# Headstage.net
KiCad netlist of a schematic drawn in Altium Designer
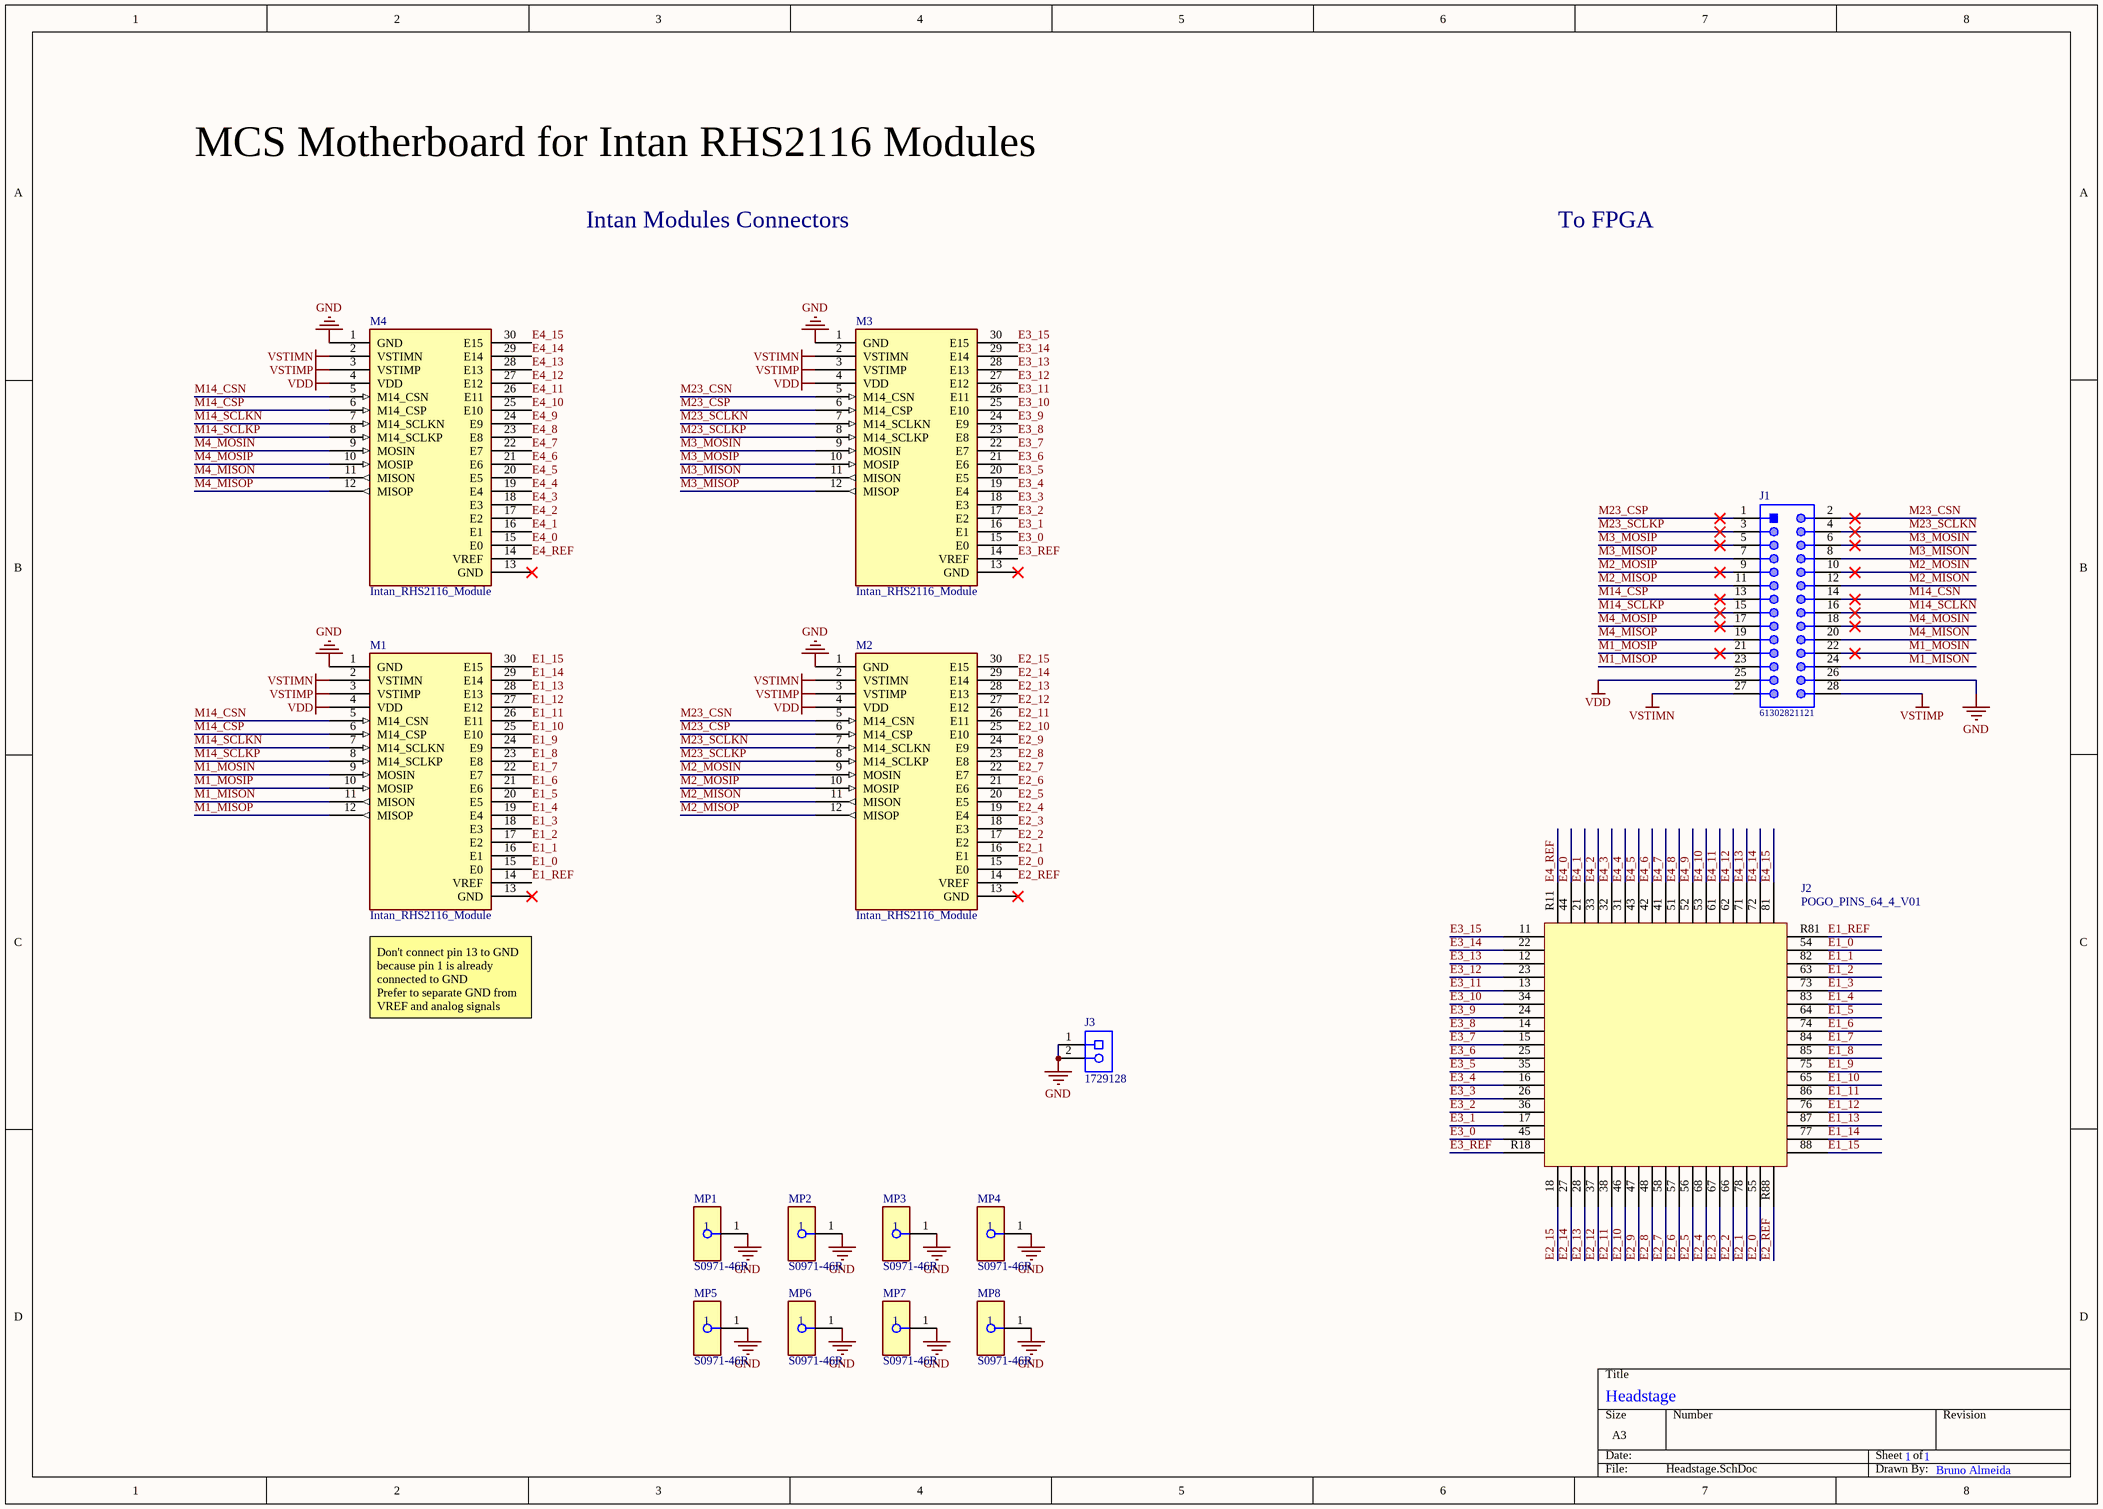
[diagram p0: Headstage.SchDoc]

(export (version "E")
  (design (tool "Eeschema 10.0.6"))
  (components
    (comp (ref "J1")
      (value "61302821121")
      (footprint "61302821121")
      (description "THT Vertical Pin Header WR-PHD, Pitch 2.54 mm, Dual Row, 28 pins")
      (fields (field (name "MANUFACTURER") "Wurth Elektronik") (field (name "PUBLISHER") "WurthElektronik"))
      (libsource (lib "Altium Content Vault") (part "WE-CN-2P-M-R28"))
    )
    (comp (ref "J2")
      (value "POGO_PINS_64_4_V01")
      (footprint "POGO_PINS_64_4_V01")
      (description "Pogo pins, 64 recording, 4 reference, v01")
      (libsource (lib "OpenMEA") (part "POGO_PINS_64_4_V01"))
    )
    (comp (ref "J3")
      (value "1729128")
      (footprint "PHOE-1729128-2_V")
      (description "PCB Terminal Block, 13.5 A, 400 V, 2-Pin THD, RoHS, Bulk")
      (fields (field (name "MANUFACTURER") "Phoenix Contact"))
      (libsource (lib "Altium Content Vault") (part "CN-2P-F-R2"))
    )
    (comp (ref "M1")
      (value "Intan_RHS2116_Module")
      (footprint "Intan_RHS2116_Module")
      (libsource (lib "V004") (part "Intan_RHS2116_Module"))
    )
    (comp (ref "M2")
      (value "Intan_RHS2116_Module")
      (footprint "Intan_RHS2116_Module")
      (libsource (lib "V004") (part "Intan_RHS2116_Module"))
    )
    (comp (ref "M3")
      (value "Intan_RHS2116_Module")
      (footprint "Intan_RHS2116_Module")
      (libsource (lib "V004") (part "Intan_RHS2116_Module"))
    )
    (comp (ref "M4")
      (value "Intan_RHS2116_Module")
      (footprint "Intan_RHS2116_Module")
      (libsource (lib "V004") (part "Intan_RHS2116_Module"))
    )
    (comp (ref "MP1")
      (value "S0971-46R")
      (footprint "FP-S0971-46R-MFG")
      (description "RFI SHIELD CLIP MINI TIN SMD")
      (fields
        (field (name "MANUFACTURER") "Harwin")
        (field (name "OCTOPART") "https://octopart.com/s0971-46r-harwin-30988305")
      )
      (libsource (lib "Altium Content Vault") (part "98815daf2f2c152b0c43f5ab9800df6"))
    )
    (comp (ref "MP2")
      (value "S0971-46R")
      (footprint "FP-S0971-46R-MFG")
      (description "RFI SHIELD CLIP MINI TIN SMD")
      (fields
        (field (name "MANUFACTURER") "Harwin")
        (field (name "OCTOPART") "https://octopart.com/s0971-46r-harwin-30988305")
      )
      (libsource (lib "Altium Content Vault") (part "98815daf2f2c152b0c43f5ab9800df6"))
    )
    (comp (ref "MP3")
      (value "S0971-46R")
      (footprint "FP-S0971-46R-MFG")
      (description "RFI SHIELD CLIP MINI TIN SMD")
      (fields
        (field (name "MANUFACTURER") "Harwin")
        (field (name "OCTOPART") "https://octopart.com/s0971-46r-harwin-30988305")
      )
      (libsource (lib "Altium Content Vault") (part "98815daf2f2c152b0c43f5ab9800df6"))
    )
    (comp (ref "MP4")
      (value "S0971-46R")
      (footprint "FP-S0971-46R-MFG")
      (description "RFI SHIELD CLIP MINI TIN SMD")
      (fields
        (field (name "MANUFACTURER") "Harwin")
        (field (name "OCTOPART") "https://octopart.com/s0971-46r-harwin-30988305")
      )
      (libsource (lib "Altium Content Vault") (part "98815daf2f2c152b0c43f5ab9800df6"))
    )
    (comp (ref "MP5")
      (value "S0971-46R")
      (footprint "FP-S0971-46R-MFG")
      (description "RFI SHIELD CLIP MINI TIN SMD")
      (fields
        (field (name "MANUFACTURER") "Harwin")
        (field (name "OCTOPART") "https://octopart.com/s0971-46r-harwin-30988305")
      )
      (libsource (lib "Altium Content Vault") (part "98815daf2f2c152b0c43f5ab9800df6"))
    )
    (comp (ref "MP6")
      (value "S0971-46R")
      (footprint "FP-S0971-46R-MFG")
      (description "RFI SHIELD CLIP MINI TIN SMD")
      (fields
        (field (name "MANUFACTURER") "Harwin")
        (field (name "OCTOPART") "https://octopart.com/s0971-46r-harwin-30988305")
      )
      (libsource (lib "Altium Content Vault") (part "98815daf2f2c152b0c43f5ab9800df6"))
    )
    (comp (ref "MP7")
      (value "S0971-46R")
      (footprint "FP-S0971-46R-MFG")
      (description "RFI SHIELD CLIP MINI TIN SMD")
      (fields
        (field (name "MANUFACTURER") "Harwin")
        (field (name "OCTOPART") "https://octopart.com/s0971-46r-harwin-30988305")
      )
      (libsource (lib "Altium Content Vault") (part "98815daf2f2c152b0c43f5ab9800df6"))
    )
    (comp (ref "MP8")
      (value "S0971-46R")
      (footprint "FP-S0971-46R-MFG")
      (description "RFI SHIELD CLIP MINI TIN SMD")
      (fields
        (field (name "MANUFACTURER") "Harwin")
        (field (name "OCTOPART") "https://octopart.com/s0971-46r-harwin-30988305")
      )
      (libsource (lib "Altium Content Vault") (part "98815daf2f2c152b0c43f5ab9800df6"))
    )
  )
  (nets
    (net (code "1") (name "/E1_0") (class "Default")
      (node (ref "J2") (pin "54") (pintype "passive"))
      (node (ref "M1") (pin "15") (pinfunction "E0_15") (pintype "passive"))
    )
    (net (code "2") (name "/E1_1") (class "Default")
      (node (ref "J2") (pin "82") (pintype "passive"))
      (node (ref "M1") (pin "16") (pinfunction "E1_16") (pintype "passive"))
    )
    (net (code "3") (name "/E1_2") (class "Default")
      (node (ref "J2") (pin "63") (pintype "passive"))
      (node (ref "M1") (pin "17") (pinfunction "E2_17") (pintype "passive"))
    )
    (net (code "4") (name "/E1_3") (class "Default")
      (node (ref "J2") (pin "73") (pintype "passive"))
      (node (ref "M1") (pin "18") (pinfunction "E3_18") (pintype "passive"))
    )
    (net (code "5") (name "/E1_4") (class "Default")
      (node (ref "J2") (pin "83") (pintype "passive"))
      (node (ref "M1") (pin "19") (pinfunction "E4_19") (pintype "passive"))
    )
    (net (code "6") (name "/E1_5") (class "Default")
      (node (ref "J2") (pin "64") (pintype "passive"))
      (node (ref "M1") (pin "20") (pinfunction "E5_20") (pintype "passive"))
    )
    (net (code "7") (name "/E1_6") (class "Default")
      (node (ref "J2") (pin "74") (pintype "passive"))
      (node (ref "M1") (pin "21") (pinfunction "E6_21") (pintype "passive"))
    )
    (net (code "8") (name "/E1_7") (class "Default")
      (node (ref "J2") (pin "84") (pintype "passive"))
      (node (ref "M1") (pin "22") (pinfunction "E7_22") (pintype "passive"))
    )
    (net (code "9") (name "/E1_8") (class "Default")
      (node (ref "J2") (pin "85") (pintype "passive"))
      (node (ref "M1") (pin "23") (pinfunction "E8_23") (pintype "passive"))
    )
    (net (code "10") (name "/E1_9") (class "Default")
      (node (ref "J2") (pin "75") (pintype "passive"))
      (node (ref "M1") (pin "24") (pinfunction "E9_24") (pintype "passive"))
    )
    (net (code "11") (name "/E1_10") (class "Default")
      (node (ref "J2") (pin "65") (pintype "passive"))
      (node (ref "M1") (pin "25") (pinfunction "E10_25") (pintype "passive"))
    )
    (net (code "12") (name "/E1_11") (class "Default")
      (node (ref "J2") (pin "86") (pintype "passive"))
      (node (ref "M1") (pin "26") (pinfunction "E11_26") (pintype "passive"))
    )
    (net (code "13") (name "/E1_12") (class "Default")
      (node (ref "J2") (pin "76") (pintype "passive"))
      (node (ref "M1") (pin "27") (pinfunction "E12_27") (pintype "passive"))
    )
    (net (code "14") (name "/E1_13") (class "Default")
      (node (ref "J2") (pin "87") (pintype "passive"))
      (node (ref "M1") (pin "28") (pinfunction "E13_28") (pintype "passive"))
    )
    (net (code "15") (name "/E1_14") (class "Default")
      (node (ref "J2") (pin "77") (pintype "passive"))
      (node (ref "M1") (pin "29") (pinfunction "E14_29") (pintype "passive"))
    )
    (net (code "16") (name "/E1_15") (class "Default")
      (node (ref "J2") (pin "88") (pintype "passive"))
      (node (ref "M1") (pin "30") (pinfunction "E15_30") (pintype "passive"))
    )
    (net (code "17") (name "/E1_REF") (class "Default")
      (node (ref "J2") (pin "R81") (pintype "passive"))
      (node (ref "M1") (pin "14") (pinfunction "VREF_14") (pintype "passive"))
    )
    (net (code "18") (name "/E2_0") (class "Default")
      (node (ref "J2") (pin "55") (pintype "passive"))
      (node (ref "M2") (pin "15") (pinfunction "E0_15") (pintype "passive"))
    )
    (net (code "19") (name "/E2_1") (class "Default")
      (node (ref "J2") (pin "78") (pintype "passive"))
      (node (ref "M2") (pin "16") (pinfunction "E1_16") (pintype "passive"))
    )
    (net (code "20") (name "/E2_2") (class "Default")
      (node (ref "J2") (pin "66") (pintype "passive"))
      (node (ref "M2") (pin "17") (pinfunction "E2_17") (pintype "passive"))
    )
    (net (code "21") (name "/E2_3") (class "Default")
      (node (ref "J2") (pin "67") (pintype "passive"))
      (node (ref "M2") (pin "18") (pinfunction "E3_18") (pintype "passive"))
    )
    (net (code "22") (name "/E2_4") (class "Default")
      (node (ref "J2") (pin "68") (pintype "passive"))
      (node (ref "M2") (pin "19") (pinfunction "E4_19") (pintype "passive"))
    )
    (net (code "23") (name "/E2_5") (class "Default")
      (node (ref "J2") (pin "56") (pintype "passive"))
      (node (ref "M2") (pin "20") (pinfunction "E5_20") (pintype "passive"))
    )
    (net (code "24") (name "/E2_6") (class "Default")
      (node (ref "J2") (pin "57") (pintype "passive"))
      (node (ref "M2") (pin "21") (pinfunction "E6_21") (pintype "passive"))
    )
    (net (code "25") (name "/E2_7") (class "Default")
      (node (ref "J2") (pin "58") (pintype "passive"))
      (node (ref "M2") (pin "22") (pinfunction "E7_22") (pintype "passive"))
    )
    (net (code "26") (name "/E2_8") (class "Default")
      (node (ref "J2") (pin "48") (pintype "passive"))
      (node (ref "M2") (pin "23") (pinfunction "E8_23") (pintype "passive"))
    )
    (net (code "27") (name "/E2_9") (class "Default")
      (node (ref "J2") (pin "47") (pintype "passive"))
      (node (ref "M2") (pin "24") (pinfunction "E9_24") (pintype "passive"))
    )
    (net (code "28") (name "/E2_10") (class "Default")
      (node (ref "J2") (pin "46") (pintype "passive"))
      (node (ref "M2") (pin "25") (pinfunction "E10_25") (pintype "passive"))
    )
    (net (code "29") (name "/E2_11") (class "Default")
      (node (ref "J2") (pin "38") (pintype "passive"))
      (node (ref "M2") (pin "26") (pinfunction "E11_26") (pintype "passive"))
    )
    (net (code "30") (name "/E2_12") (class "Default")
      (node (ref "J2") (pin "37") (pintype "passive"))
      (node (ref "M2") (pin "27") (pinfunction "E12_27") (pintype "passive"))
    )
    (net (code "31") (name "/E2_13") (class "Default")
      (node (ref "J2") (pin "28") (pintype "passive"))
      (node (ref "M2") (pin "28") (pinfunction "E13_28") (pintype "passive"))
    )
    (net (code "32") (name "/E2_14") (class "Default")
      (node (ref "J2") (pin "27") (pintype "passive"))
      (node (ref "M2") (pin "29") (pinfunction "E14_29") (pintype "passive"))
    )
    (net (code "33") (name "/E2_15") (class "Default")
      (node (ref "J2") (pin "18") (pintype "passive"))
      (node (ref "M2") (pin "30") (pinfunction "E15_30") (pintype "passive"))
    )
    (net (code "34") (name "/E2_REF") (class "Default")
      (node (ref "J2") (pin "R88") (pintype "passive"))
      (node (ref "M2") (pin "14") (pinfunction "VREF_14") (pintype "passive"))
    )
    (net (code "35") (name "/E3_0") (class "Default")
      (node (ref "J2") (pin "45") (pintype "passive"))
      (node (ref "M3") (pin "15") (pinfunction "E0_15") (pintype "passive"))
    )
    (net (code "36") (name "/E3_1") (class "Default")
      (node (ref "J2") (pin "17") (pintype "passive"))
      (node (ref "M3") (pin "16") (pinfunction "E1_16") (pintype "passive"))
    )
    (net (code "37") (name "/E3_2") (class "Default")
      (node (ref "J2") (pin "36") (pintype "passive"))
      (node (ref "M3") (pin "17") (pinfunction "E2_17") (pintype "passive"))
    )
    (net (code "38") (name "/E3_3") (class "Default")
      (node (ref "J2") (pin "26") (pintype "passive"))
      (node (ref "M3") (pin "18") (pinfunction "E3_18") (pintype "passive"))
    )
    (net (code "39") (name "/E3_4") (class "Default")
      (node (ref "J2") (pin "16") (pintype "passive"))
      (node (ref "M3") (pin "19") (pinfunction "E4_19") (pintype "passive"))
    )
    (net (code "40") (name "/E3_5") (class "Default")
      (node (ref "J2") (pin "35") (pintype "passive"))
      (node (ref "M3") (pin "20") (pinfunction "E5_20") (pintype "passive"))
    )
    (net (code "41") (name "/E3_6") (class "Default")
      (node (ref "J2") (pin "25") (pintype "passive"))
      (node (ref "M3") (pin "21") (pinfunction "E6_21") (pintype "passive"))
    )
    (net (code "42") (name "/E3_7") (class "Default")
      (node (ref "J2") (pin "15") (pintype "passive"))
      (node (ref "M3") (pin "22") (pinfunction "E7_22") (pintype "passive"))
    )
    (net (code "43") (name "/E3_8") (class "Default")
      (node (ref "J2") (pin "14") (pintype "passive"))
      (node (ref "M3") (pin "23") (pinfunction "E8_23") (pintype "passive"))
    )
    (net (code "44") (name "/E3_9") (class "Default")
      (node (ref "J2") (pin "24") (pintype "passive"))
      (node (ref "M3") (pin "24") (pinfunction "E9_24") (pintype "passive"))
    )
    (net (code "45") (name "/E3_10") (class "Default")
      (node (ref "J2") (pin "34") (pintype "passive"))
      (node (ref "M3") (pin "25") (pinfunction "E10_25") (pintype "passive"))
    )
    (net (code "46") (name "/E3_11") (class "Default")
      (node (ref "J2") (pin "13") (pintype "passive"))
      (node (ref "M3") (pin "26") (pinfunction "E11_26") (pintype "passive"))
    )
    (net (code "47") (name "/E3_12") (class "Default")
      (node (ref "J2") (pin "23") (pintype "passive"))
      (node (ref "M3") (pin "27") (pinfunction "E12_27") (pintype "passive"))
    )
    (net (code "48") (name "/E3_13") (class "Default")
      (node (ref "J2") (pin "12") (pintype "passive"))
      (node (ref "M3") (pin "28") (pinfunction "E13_28") (pintype "passive"))
    )
    (net (code "49") (name "/E3_14") (class "Default")
      (node (ref "J2") (pin "22") (pintype "passive"))
      (node (ref "M3") (pin "29") (pinfunction "E14_29") (pintype "passive"))
    )
    (net (code "50") (name "/E3_15") (class "Default")
      (node (ref "J2") (pin "11") (pintype "passive"))
      (node (ref "M3") (pin "30") (pinfunction "E15_30") (pintype "passive"))
    )
    (net (code "51") (name "/E3_REF") (class "Default")
      (node (ref "J2") (pin "R18") (pintype "passive"))
      (node (ref "M3") (pin "14") (pinfunction "VREF_14") (pintype "passive"))
    )
    (net (code "52") (name "/E4_0") (class "Default")
      (node (ref "J2") (pin "44") (pintype "passive"))
      (node (ref "M4") (pin "15") (pinfunction "E0_15") (pintype "passive"))
    )
    (net (code "53") (name "/E4_1") (class "Default")
      (node (ref "J2") (pin "21") (pintype "passive"))
      (node (ref "M4") (pin "16") (pinfunction "E1_16") (pintype "passive"))
    )
    (net (code "54") (name "/E4_2") (class "Default")
      (node (ref "J2") (pin "33") (pintype "passive"))
      (node (ref "M4") (pin "17") (pinfunction "E2_17") (pintype "passive"))
    )
    (net (code "55") (name "/E4_3") (class "Default")
      (node (ref "J2") (pin "32") (pintype "passive"))
      (node (ref "M4") (pin "18") (pinfunction "E3_18") (pintype "passive"))
    )
    (net (code "56") (name "/E4_4") (class "Default")
      (node (ref "J2") (pin "31") (pintype "passive"))
      (node (ref "M4") (pin "19") (pinfunction "E4_19") (pintype "passive"))
    )
    (net (code "57") (name "/E4_5") (class "Default")
      (node (ref "J2") (pin "43") (pintype "passive"))
      (node (ref "M4") (pin "20") (pinfunction "E5_20") (pintype "passive"))
    )
    (net (code "58") (name "/E4_6") (class "Default")
      (node (ref "J2") (pin "42") (pintype "passive"))
      (node (ref "M4") (pin "21") (pinfunction "E6_21") (pintype "passive"))
    )
    (net (code "59") (name "/E4_7") (class "Default")
      (node (ref "J2") (pin "41") (pintype "passive"))
      (node (ref "M4") (pin "22") (pinfunction "E7_22") (pintype "passive"))
    )
    (net (code "60") (name "/E4_8") (class "Default")
      (node (ref "J2") (pin "51") (pintype "passive"))
      (node (ref "M4") (pin "23") (pinfunction "E8_23") (pintype "passive"))
    )
    (net (code "61") (name "/E4_9") (class "Default")
      (node (ref "J2") (pin "52") (pintype "passive"))
      (node (ref "M4") (pin "24") (pinfunction "E9_24") (pintype "passive"))
    )
    (net (code "62") (name "/E4_10") (class "Default")
      (node (ref "J2") (pin "53") (pintype "passive"))
      (node (ref "M4") (pin "25") (pinfunction "E10_25") (pintype "passive"))
    )
    (net (code "63") (name "/E4_11") (class "Default")
      (node (ref "J2") (pin "61") (pintype "passive"))
      (node (ref "M4") (pin "26") (pinfunction "E11_26") (pintype "passive"))
    )
    (net (code "64") (name "/E4_12") (class "Default")
      (node (ref "J2") (pin "62") (pintype "passive"))
      (node (ref "M4") (pin "27") (pinfunction "E12_27") (pintype "passive"))
    )
    (net (code "65") (name "/E4_13") (class "Default")
      (node (ref "J2") (pin "71") (pintype "passive"))
      (node (ref "M4") (pin "28") (pinfunction "E13_28") (pintype "passive"))
    )
    (net (code "66") (name "/E4_14") (class "Default")
      (node (ref "J2") (pin "72") (pintype "passive"))
      (node (ref "M4") (pin "29") (pinfunction "E14_29") (pintype "passive"))
    )
    (net (code "67") (name "/E4_15") (class "Default")
      (node (ref "J2") (pin "81") (pintype "passive"))
      (node (ref "M4") (pin "30") (pinfunction "E15_30") (pintype "passive"))
    )
    (net (code "68") (name "/E4_REF") (class "Default")
      (node (ref "J2") (pin "R11") (pintype "passive"))
      (node (ref "M4") (pin "14") (pinfunction "VREF_14") (pintype "passive"))
    )
    (net (code "69") (name "/M1_MISON") (class "Default")
      (node (ref "J1") (pin "24") (pinfunction "24_24") (pintype "passive"))
      (node (ref "M1") (pin "11") (pinfunction "MISON_11") (pintype "output"))
    )
    (net (code "70") (name "/M1_MISOP") (class "Default")
      (node (ref "J1") (pin "23") (pinfunction "23_23") (pintype "passive"))
      (node (ref "M1") (pin "12") (pinfunction "MISOP_12") (pintype "output"))
    )
    (net (code "71") (name "/M1_MOSIN") (class "Default")
      (node (ref "J1") (pin "22") (pinfunction "22_22") (pintype "passive"))
      (node (ref "M1") (pin "9") (pinfunction "MOSIN_9") (pintype "input"))
    )
    (net (code "72") (name "/M1_MOSIP") (class "Default")
      (node (ref "J1") (pin "21") (pinfunction "21_21") (pintype "passive"))
      (node (ref "M1") (pin "10") (pinfunction "MOSIP_10") (pintype "input"))
    )
    (net (code "73") (name "/M2_MISON") (class "Default")
      (node (ref "J1") (pin "12") (pinfunction "12_12") (pintype "passive"))
      (node (ref "M2") (pin "11") (pinfunction "MISON_11") (pintype "output"))
    )
    (net (code "74") (name "/M2_MISOP") (class "Default")
      (node (ref "J1") (pin "11") (pinfunction "11_11") (pintype "passive"))
      (node (ref "M2") (pin "12") (pinfunction "MISOP_12") (pintype "output"))
    )
    (net (code "75") (name "/M2_MOSIN") (class "Default")
      (node (ref "J1") (pin "10") (pinfunction "10_10") (pintype "passive"))
      (node (ref "M2") (pin "9") (pinfunction "MOSIN_9") (pintype "input"))
    )
    (net (code "76") (name "/M2_MOSIP") (class "Default")
      (node (ref "J1") (pin "9") (pinfunction "9_9") (pintype "passive"))
      (node (ref "M2") (pin "10") (pinfunction "MOSIP_10") (pintype "input"))
    )
    (net (code "77") (name "/M3_MISON") (class "Default")
      (node (ref "J1") (pin "8") (pinfunction "8_8") (pintype "passive"))
      (node (ref "M3") (pin "11") (pinfunction "MISON_11") (pintype "output"))
    )
    (net (code "78") (name "/M3_MISOP") (class "Default")
      (node (ref "J1") (pin "7") (pinfunction "7_7") (pintype "passive"))
      (node (ref "M3") (pin "12") (pinfunction "MISOP_12") (pintype "output"))
    )
    (net (code "79") (name "/M3_MOSIN") (class "Default")
      (node (ref "J1") (pin "6") (pinfunction "6_6") (pintype "passive"))
      (node (ref "M3") (pin "9") (pinfunction "MOSIN_9") (pintype "input"))
    )
    (net (code "80") (name "/M3_MOSIP") (class "Default")
      (node (ref "J1") (pin "5") (pinfunction "5_5") (pintype "passive"))
      (node (ref "M3") (pin "10") (pinfunction "MOSIP_10") (pintype "input"))
    )
    (net (code "81") (name "/M4_MISON") (class "Default")
      (node (ref "J1") (pin "20") (pinfunction "20_20") (pintype "passive"))
      (node (ref "M4") (pin "11") (pinfunction "MISON_11") (pintype "output"))
    )
    (net (code "82") (name "/M4_MISOP") (class "Default")
      (node (ref "J1") (pin "19") (pinfunction "19_19") (pintype "passive"))
      (node (ref "M4") (pin "12") (pinfunction "MISOP_12") (pintype "output"))
    )
    (net (code "83") (name "/M4_MOSIN") (class "Default")
      (node (ref "J1") (pin "18") (pinfunction "18_18") (pintype "passive"))
      (node (ref "M4") (pin "9") (pinfunction "MOSIN_9") (pintype "input"))
    )
    (net (code "84") (name "/M4_MOSIP") (class "Default")
      (node (ref "J1") (pin "17") (pinfunction "17_17") (pintype "passive"))
      (node (ref "M4") (pin "10") (pinfunction "MOSIP_10") (pintype "input"))
    )
    (net (code "85") (name "/M14_CSN") (class "Default")
      (node (ref "J1") (pin "14") (pinfunction "14_14") (pintype "passive"))
      (node (ref "M1") (pin "5") (pinfunction "M14_CSN_5") (pintype "input"))
      (node (ref "M4") (pin "5") (pinfunction "M14_CSN_5") (pintype "input"))
    )
    (net (code "86") (name "/M14_CSP") (class "Default")
      (node (ref "J1") (pin "13") (pinfunction "13_13") (pintype "passive"))
      (node (ref "M1") (pin "6") (pinfunction "M14_CSP_6") (pintype "input"))
      (node (ref "M4") (pin "6") (pinfunction "M14_CSP_6") (pintype "input"))
    )
    (net (code "87") (name "/M14_SCLKN") (class "Default")
      (node (ref "J1") (pin "16") (pinfunction "16_16") (pintype "passive"))
      (node (ref "M1") (pin "7") (pinfunction "M14_SCLKN_7") (pintype "input"))
      (node (ref "M4") (pin "7") (pinfunction "M14_SCLKN_7") (pintype "input"))
    )
    (net (code "88") (name "/M14_SCLKP") (class "Default")
      (node (ref "J1") (pin "15") (pinfunction "15_15") (pintype "passive"))
      (node (ref "M1") (pin "8") (pinfunction "M14_SCLKP_8") (pintype "input"))
      (node (ref "M4") (pin "8") (pinfunction "M14_SCLKP_8") (pintype "input"))
    )
    (net (code "89") (name "/M23_CSN") (class "Default")
      (node (ref "J1") (pin "2") (pinfunction "2_2") (pintype "passive"))
      (node (ref "M2") (pin "5") (pinfunction "M14_CSN_5") (pintype "input"))
      (node (ref "M3") (pin "5") (pinfunction "M14_CSN_5") (pintype "input"))
    )
    (net (code "90") (name "/M23_CSP") (class "Default")
      (node (ref "J1") (pin "1") (pinfunction "1_1") (pintype "passive"))
      (node (ref "M2") (pin "6") (pinfunction "M14_CSP_6") (pintype "input"))
      (node (ref "M3") (pin "6") (pinfunction "M14_CSP_6") (pintype "input"))
    )
    (net (code "91") (name "/M23_SCLKN") (class "Default")
      (node (ref "J1") (pin "4") (pinfunction "4_4") (pintype "passive"))
      (node (ref "M2") (pin "7") (pinfunction "M14_SCLKN_7") (pintype "input"))
      (node (ref "M3") (pin "7") (pinfunction "M14_SCLKN_7") (pintype "input"))
    )
    (net (code "92") (name "/M23_SCLKP") (class "Default")
      (node (ref "J1") (pin "3") (pinfunction "3_3") (pintype "passive"))
      (node (ref "M2") (pin "8") (pinfunction "M14_SCLKP_8") (pintype "input"))
      (node (ref "M3") (pin "8") (pinfunction "M14_SCLKP_8") (pintype "input"))
    )
    (net (code "93") (name "GND") (class "Default")
      (node (ref "J1") (pin "26") (pinfunction "26_26") (pintype "passive"))
      (node (ref "J3") (pin "1") (pinfunction "1_1") (pintype "passive"))
      (node (ref "J3") (pin "2") (pinfunction "2_2") (pintype "passive"))
      (node (ref "M1") (pin "1") (pinfunction "GND_1") (pintype "power_in"))
      (node (ref "M2") (pin "1") (pinfunction "GND_1") (pintype "power_in"))
      (node (ref "M3") (pin "1") (pinfunction "GND_1") (pintype "power_in"))
      (node (ref "M4") (pin "1") (pinfunction "GND_1") (pintype "power_in"))
      (node (ref "MP1") (pin "1") (pinfunction "1_1") (pintype "passive"))
      (node (ref "MP2") (pin "1") (pinfunction "1_1") (pintype "passive"))
      (node (ref "MP3") (pin "1") (pinfunction "1_1") (pintype "passive"))
      (node (ref "MP4") (pin "1") (pinfunction "1_1") (pintype "passive"))
      (node (ref "MP5") (pin "1") (pinfunction "1_1") (pintype "passive"))
      (node (ref "MP6") (pin "1") (pinfunction "1_1") (pintype "passive"))
      (node (ref "MP7") (pin "1") (pinfunction "1_1") (pintype "passive"))
      (node (ref "MP8") (pin "1") (pinfunction "1_1") (pintype "passive"))
    )
    (net (code "94") (name "VDD") (class "Default")
      (node (ref "J1") (pin "25") (pinfunction "25_25") (pintype "passive"))
      (node (ref "M1") (pin "4") (pinfunction "VDD_4") (pintype "power_in"))
      (node (ref "M2") (pin "4") (pinfunction "VDD_4") (pintype "power_in"))
      (node (ref "M3") (pin "4") (pinfunction "VDD_4") (pintype "power_in"))
      (node (ref "M4") (pin "4") (pinfunction "VDD_4") (pintype "power_in"))
    )
    (net (code "95") (name "VSTIMN") (class "Default")
      (node (ref "J1") (pin "27") (pinfunction "27_27") (pintype "passive"))
      (node (ref "M1") (pin "2") (pinfunction "VSTIMN_2") (pintype "power_in"))
      (node (ref "M2") (pin "2") (pinfunction "VSTIMN_2") (pintype "power_in"))
      (node (ref "M3") (pin "2") (pinfunction "VSTIMN_2") (pintype "power_in"))
      (node (ref "M4") (pin "2") (pinfunction "VSTIMN_2") (pintype "power_in"))
    )
    (net (code "96") (name "VSTIMP") (class "Default")
      (node (ref "J1") (pin "28") (pinfunction "28_28") (pintype "passive"))
      (node (ref "M1") (pin "3") (pinfunction "VSTIMP_3") (pintype "power_in"))
      (node (ref "M2") (pin "3") (pinfunction "VSTIMP_3") (pintype "power_in"))
      (node (ref "M3") (pin "3") (pinfunction "VSTIMP_3") (pintype "power_in"))
      (node (ref "M4") (pin "3") (pinfunction "VSTIMP_3") (pintype "power_in"))
    )
    (net (code "97") (name "unconnected-(M1-GND-Pad13)") (class "Default")
      (node (ref "M1") (pin "13") (pinfunction "GND_13") (pintype "power_in+no_connect"))
    )
    (net (code "98") (name "unconnected-(M2-GND-Pad13)") (class "Default")
      (node (ref "M2") (pin "13") (pinfunction "GND_13") (pintype "power_in+no_connect"))
    )
    (net (code "99") (name "unconnected-(M3-GND-Pad13)") (class "Default")
      (node (ref "M3") (pin "13") (pinfunction "GND_13") (pintype "power_in+no_connect"))
    )
    (net (code "100") (name "unconnected-(M4-GND-Pad13)") (class "Default")
      (node (ref "M4") (pin "13") (pinfunction "GND_13") (pintype "power_in+no_connect"))
    )
  )
)
